# analog_in.net
KiCad netlist of a schematic drawn in Altium Designer
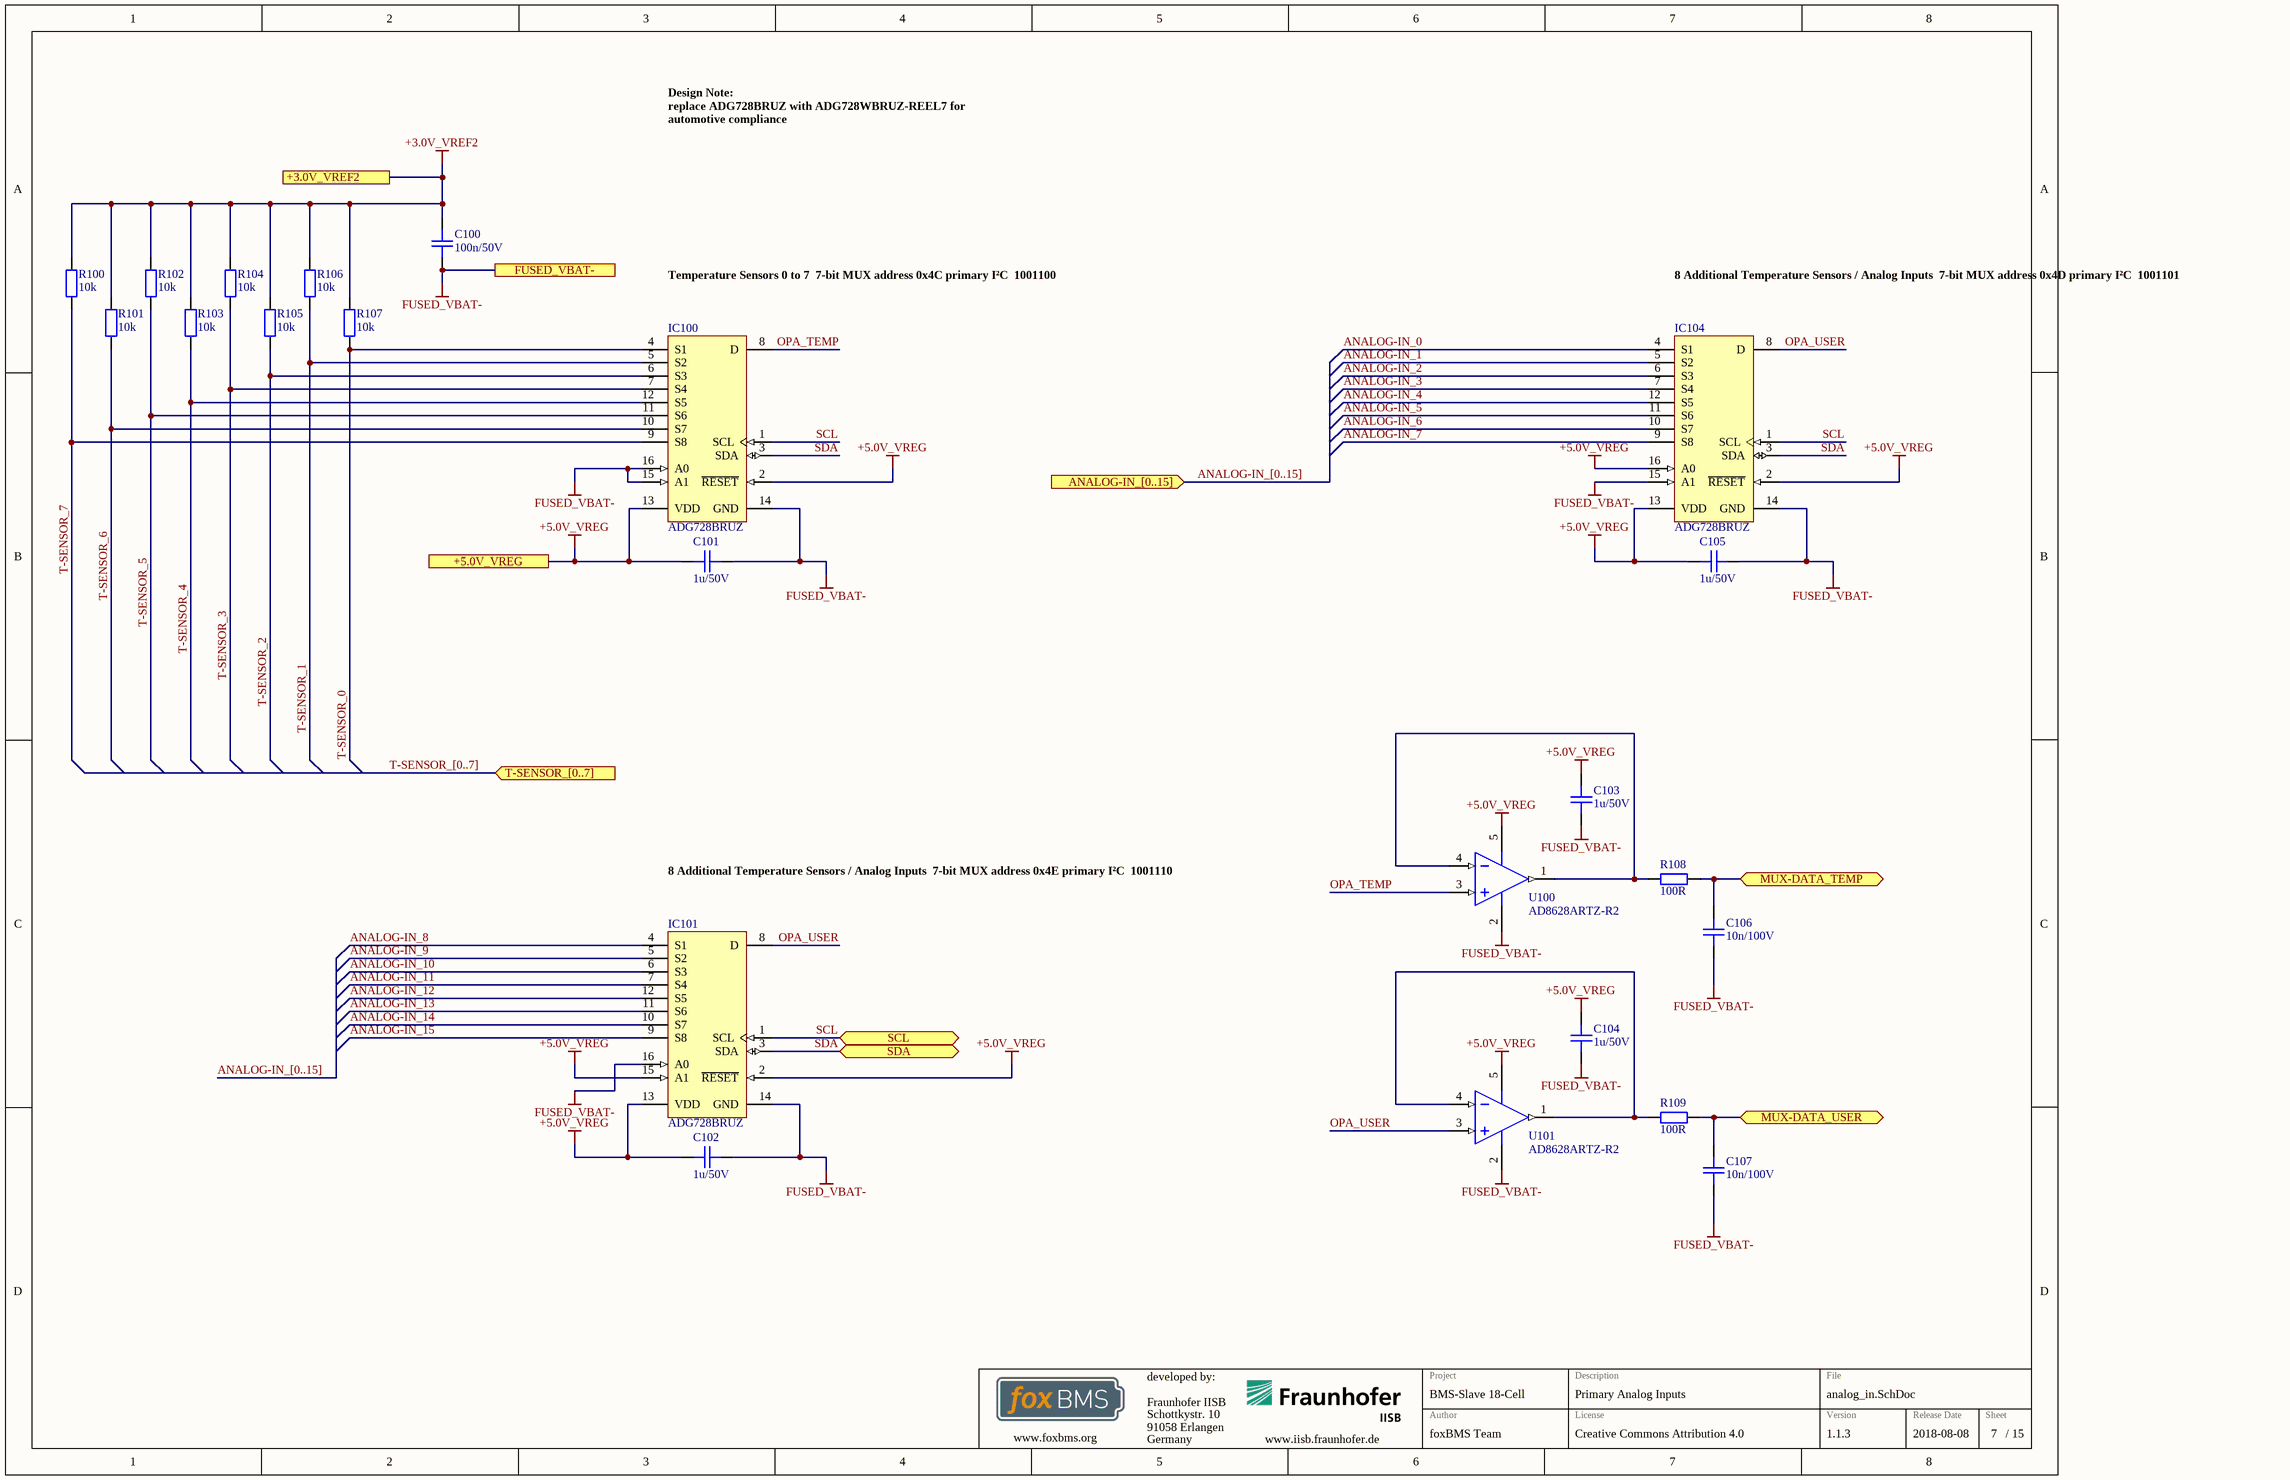
[diagram p0: analog_in.SchDoc]

(export (version "E")
  (design (tool "Eeschema 10.0.6"))
  (components
    (comp (ref "C100")
      (value "100n/50V")
      (footprint "CAPC1608X08N")
      (description "MLCC")
      (fields (field (name "PART NUMBER") "gen_C_ceramic_100n_50V_X7R_0603"))
      (libsource (lib "OE750") (part "C"))
    )
    (comp (ref "C101")
      (value "1u/50V")
      (footprint "CAPC2012X14N")
      (description "MLCC")
      (fields (field (name "PART NUMBER") "gen_C_ceramic_1u_50V_X7R_0805") (field (name "TOLERANCE") "± 10%"))
      (libsource (lib "OE750") (part "C"))
    )
    (comp (ref "C102")
      (value "1u/50V")
      (footprint "CAPC2012X14N")
      (description "MLCC")
      (fields (field (name "PART NUMBER") "gen_C_ceramic_1u_50V_X7R_0805") (field (name "TOLERANCE") "± 10%"))
      (libsource (lib "OE750") (part "C"))
    )
    (comp (ref "C103")
      (value "1u/50V")
      (footprint "CAPC2012X14N")
      (description "MLCC")
      (fields (field (name "PART NUMBER") "gen_C_ceramic_1u_50V_X7R_0805") (field (name "TOLERANCE") "± 10%"))
      (libsource (lib "OE750") (part "C"))
    )
    (comp (ref "C104")
      (value "1u/50V")
      (footprint "CAPC2012X14N")
      (description "MLCC")
      (fields (field (name "PART NUMBER") "gen_C_ceramic_1u_50V_X7R_0805") (field (name "TOLERANCE") "± 10%"))
      (libsource (lib "OE750") (part "C"))
    )
    (comp (ref "C105")
      (value "1u/50V")
      (footprint "CAPC2012X14N")
      (description "MLCC")
      (fields (field (name "PART NUMBER") "gen_C_ceramic_1u_50V_X7R_0805") (field (name "TOLERANCE") "± 10%"))
      (libsource (lib "OE750") (part "C"))
    )
    (comp (ref "C106")
      (value "10n/100V")
      (footprint "CAPC1608X08N")
      (description "MLCC")
      (fields (field (name "PART NUMBER") "gen_C_ceramic_10n_100V_X7R_0603"))
      (libsource (lib "OE750") (part "C"))
    )
    (comp (ref "C107")
      (value "10n/100V")
      (footprint "CAPC1608X08N")
      (description "MLCC")
      (fields (field (name "PART NUMBER") "gen_C_ceramic_10n_100V_X7R_0603"))
      (libsource (lib "OE750") (part "C"))
    )
    (comp (ref "IC100")
      (value "ADG728BRUZ")
      (footprint "ADI-RU-16_M")
      (fields (field (name "MANUFACTURER") "Analog Devices"))
      (libsource (lib "Altium Content Vault") (part "ADI-ADG728-RU-16"))
    )
    (comp (ref "IC101")
      (value "ADG728BRUZ")
      (footprint "ADI-RU-16_M")
      (fields (field (name "MANUFACTURER") "Analog Devices"))
      (libsource (lib "Altium Content Vault") (part "ADI-ADG728-RU-16"))
    )
    (comp (ref "IC104")
      (value "ADG728BRUZ")
      (footprint "ADI-RU-16_M")
      (fields (field (name "MANUFACTURER") "Analog Devices"))
      (libsource (lib "Altium Content Vault") (part "ADI-ADG728-RU-16"))
    )
    (comp (ref "R100")
      (value "10k")
      (footprint "RESC1608X05N")
      (description "SMD Resistor 10k 0603")
      (fields (field (name "PART NUMBER") "gen_R_10k_0603") (field (name "TOLERANCE") "1%"))
      (libsource (lib "OE750") (part "R"))
    )
    (comp (ref "R101")
      (value "10k")
      (footprint "RESC1608X05N")
      (description "SMD Resistor 10k 0603")
      (fields (field (name "PART NUMBER") "gen_R_10k_0603") (field (name "TOLERANCE") "1%"))
      (libsource (lib "OE750") (part "R"))
    )
    (comp (ref "R102")
      (value "10k")
      (footprint "RESC1608X05N")
      (description "SMD Resistor 10k 0603")
      (fields (field (name "PART NUMBER") "gen_R_10k_0603") (field (name "TOLERANCE") "1%"))
      (libsource (lib "OE750") (part "R"))
    )
    (comp (ref "R103")
      (value "10k")
      (footprint "RESC1608X05N")
      (description "SMD Resistor 10k 0603")
      (fields (field (name "PART NUMBER") "gen_R_10k_0603") (field (name "TOLERANCE") "1%"))
      (libsource (lib "OE750") (part "R"))
    )
    (comp (ref "R104")
      (value "10k")
      (footprint "RESC1608X05N")
      (description "SMD Resistor 10k 0603")
      (fields (field (name "PART NUMBER") "gen_R_10k_0603") (field (name "TOLERANCE") "1%"))
      (libsource (lib "OE750") (part "R"))
    )
    (comp (ref "R105")
      (value "10k")
      (footprint "RESC1608X05N")
      (description "SMD Resistor 10k 0603")
      (fields (field (name "PART NUMBER") "gen_R_10k_0603") (field (name "TOLERANCE") "1%"))
      (libsource (lib "OE750") (part "R"))
    )
    (comp (ref "R106")
      (value "10k")
      (footprint "RESC1608X05N")
      (description "SMD Resistor 10k 0603")
      (fields (field (name "PART NUMBER") "gen_R_10k_0603") (field (name "TOLERANCE") "1%"))
      (libsource (lib "OE750") (part "R"))
    )
    (comp (ref "R107")
      (value "10k")
      (footprint "RESC1608X05N")
      (description "SMD Resistor 10k 0603")
      (fields (field (name "PART NUMBER") "gen_R_10k_0603") (field (name "TOLERANCE") "1%"))
      (libsource (lib "OE750") (part "R"))
    )
    (comp (ref "R108")
      (value "100R")
      (footprint "RESC1608X05N")
      (description "SMD Resistor 100R 0603")
      (fields (field (name "PART NUMBER") "gen_R_100R_0603") (field (name "TOLERANCE") "1%"))
      (libsource (lib "OE750") (part "R"))
    )
    (comp (ref "R109")
      (value "100R")
      (footprint "RESC1608X05N")
      (description "SMD Resistor 100R 0603")
      (fields (field (name "PART NUMBER") "gen_R_100R_0603") (field (name "TOLERANCE") "1%"))
      (libsource (lib "OE750") (part "R"))
    )
    (comp (ref "U100")
      (value "AD8628ARTZ-R2")
      (footprint "ADI-RJ-5_M")
      (fields (field (name "MANUFACTURER") "Analog Devices") (field (name "GENERIC PART NUMBER") "AD8628"))
      (libsource (lib "Altium Content Vault") (part "ADI-ADxxxx-X-5"))
    )
    (comp (ref "U101")
      (value "AD8628ARTZ-R2")
      (footprint "ADI-RJ-5_M")
      (fields (field (name "MANUFACTURER") "Analog Devices") (field (name "GENERIC PART NUMBER") "AD8628"))
      (libsource (lib "Altium Content Vault") (part "ADI-ADxxxx-X-5"))
    )
  )
  (nets
    (net (code "1") (name "+3.0V_VREF2") (class "Default")
      (node (ref "C100") (pin "2") (pinfunction "2_2") (pintype "passive"))
      (node (ref "R100") (pin "2") (pinfunction "2_2") (pintype "passive"))
      (node (ref "R101") (pin "2") (pinfunction "2_2") (pintype "passive"))
      (node (ref "R102") (pin "2") (pinfunction "2_2") (pintype "passive"))
      (node (ref "R103") (pin "2") (pinfunction "2_2") (pintype "passive"))
      (node (ref "R104") (pin "2") (pinfunction "2_2") (pintype "passive"))
      (node (ref "R105") (pin "2") (pinfunction "2_2") (pintype "passive"))
      (node (ref "R106") (pin "2") (pinfunction "2_2") (pintype "passive"))
      (node (ref "R107") (pin "2") (pinfunction "2_2") (pintype "passive"))
    )
    (net (code "2") (name "+5.0V_VREG") (class "Default")
      (node (ref "C101") (pin "2") (pinfunction "2_2") (pintype "passive"))
      (node (ref "C102") (pin "2") (pinfunction "2_2") (pintype "passive"))
      (node (ref "C103") (pin "2") (pinfunction "2_2") (pintype "passive"))
      (node (ref "C104") (pin "2") (pinfunction "2_2") (pintype "passive"))
      (node (ref "C105") (pin "2") (pinfunction "2_2") (pintype "passive"))
      (node (ref "IC100") (pin "13") (pinfunction "VDD_13") (pintype "power_in"))
      (node (ref "IC100") (pin "2") (pinfunction "~{RESET}_2") (pintype "input"))
      (node (ref "IC101") (pin "13") (pinfunction "VDD_13") (pintype "power_in"))
      (node (ref "IC101") (pin "15") (pinfunction "A1_15") (pintype "input"))
      (node (ref "IC101") (pin "2") (pinfunction "~{RESET}_2") (pintype "input"))
      (node (ref "IC104") (pin "13") (pinfunction "VDD_13") (pintype "power_in"))
      (node (ref "IC104") (pin "16") (pinfunction "A0_16") (pintype "input"))
      (node (ref "IC104") (pin "2") (pinfunction "~{RESET}_2") (pintype "input"))
      (node (ref "U100") (pin "5") (pinfunction "+V_5") (pintype "power_in"))
      (node (ref "U101") (pin "5") (pinfunction "+V_5") (pintype "power_in"))
    )
    (net (code "3") (name "/ANALOG-IN_0") (class "Default")
      (node (ref "IC104") (pin "4") (pinfunction "S1_4") (pintype "passive"))
    )
    (net (code "4") (name "/ANALOG-IN_1") (class "Default")
      (node (ref "IC104") (pin "5") (pinfunction "S2_5") (pintype "passive"))
    )
    (net (code "5") (name "/ANALOG-IN_2") (class "Default")
      (node (ref "IC104") (pin "6") (pinfunction "S3_6") (pintype "passive"))
    )
    (net (code "6") (name "/ANALOG-IN_3") (class "Default")
      (node (ref "IC104") (pin "7") (pinfunction "S4_7") (pintype "passive"))
    )
    (net (code "7") (name "/ANALOG-IN_4") (class "Default")
      (node (ref "IC104") (pin "12") (pinfunction "S5_12") (pintype "passive"))
    )
    (net (code "8") (name "/ANALOG-IN_5") (class "Default")
      (node (ref "IC104") (pin "11") (pinfunction "S6_11") (pintype "passive"))
    )
    (net (code "9") (name "/ANALOG-IN_6") (class "Default")
      (node (ref "IC104") (pin "10") (pinfunction "S7_10") (pintype "passive"))
    )
    (net (code "10") (name "/ANALOG-IN_7") (class "Default")
      (node (ref "IC104") (pin "9") (pinfunction "S8_9") (pintype "passive"))
    )
    (net (code "11") (name "/ANALOG-IN_8") (class "Default")
      (node (ref "IC101") (pin "4") (pinfunction "S1_4") (pintype "passive"))
    )
    (net (code "12") (name "/ANALOG-IN_9") (class "Default")
      (node (ref "IC101") (pin "5") (pinfunction "S2_5") (pintype "passive"))
    )
    (net (code "13") (name "/ANALOG-IN_10") (class "Default")
      (node (ref "IC101") (pin "6") (pinfunction "S3_6") (pintype "passive"))
    )
    (net (code "14") (name "/ANALOG-IN_11") (class "Default")
      (node (ref "IC101") (pin "7") (pinfunction "S4_7") (pintype "passive"))
    )
    (net (code "15") (name "/ANALOG-IN_12") (class "Default")
      (node (ref "IC101") (pin "12") (pinfunction "S5_12") (pintype "passive"))
    )
    (net (code "16") (name "/ANALOG-IN_13") (class "Default")
      (node (ref "IC101") (pin "11") (pinfunction "S6_11") (pintype "passive"))
    )
    (net (code "17") (name "/ANALOG-IN_14") (class "Default")
      (node (ref "IC101") (pin "10") (pinfunction "S7_10") (pintype "passive"))
    )
    (net (code "18") (name "/ANALOG-IN_15") (class "Default")
      (node (ref "IC101") (pin "9") (pinfunction "S8_9") (pintype "passive"))
    )
    (net (code "20") (name "/MUX-DATA_TEMP") (class "Default")
      (node (ref "C106") (pin "2") (pinfunction "2_2") (pintype "passive"))
      (node (ref "R108") (pin "2") (pinfunction "2_2") (pintype "passive"))
    )
    (net (code "21") (name "/MUX-DATA_USER") (class "Default")
      (node (ref "C107") (pin "2") (pinfunction "2_2") (pintype "passive"))
      (node (ref "R109") (pin "2") (pinfunction "2_2") (pintype "passive"))
    )
    (net (code "22") (name "/OPA_TEMP") (class "Default")
      (node (ref "IC100") (pin "8") (pinfunction "D_8") (pintype "passive"))
      (node (ref "U100") (pin "3") (pinfunction "+IN_3") (pintype "input"))
    )
    (net (code "23") (name "/OPA_USER") (class "Default")
      (node (ref "IC101") (pin "8") (pinfunction "D_8") (pintype "passive"))
      (node (ref "IC104") (pin "8") (pinfunction "D_8") (pintype "passive"))
      (node (ref "U101") (pin "3") (pinfunction "+IN_3") (pintype "input"))
    )
    (net (code "24") (name "/SCL") (class "Default")
      (node (ref "IC100") (pin "1") (pinfunction "SCL_1") (pintype "input"))
      (node (ref "IC101") (pin "1") (pinfunction "SCL_1") (pintype "input"))
      (node (ref "IC104") (pin "1") (pinfunction "SCL_1") (pintype "input"))
    )
    (net (code "25") (name "/SDA") (class "Default")
      (node (ref "IC100") (pin "3") (pinfunction "SDA_3") (pintype "bidirectional"))
      (node (ref "IC101") (pin "3") (pinfunction "SDA_3") (pintype "bidirectional"))
      (node (ref "IC104") (pin "3") (pinfunction "SDA_3") (pintype "bidirectional"))
    )
    (net (code "26") (name "/T-SENSOR_0") (class "Default")
      (node (ref "IC100") (pin "4") (pinfunction "S1_4") (pintype "passive"))
      (node (ref "R107") (pin "1") (pinfunction "1_1") (pintype "passive"))
    )
    (net (code "27") (name "/T-SENSOR_1") (class "Default")
      (node (ref "IC100") (pin "5") (pinfunction "S2_5") (pintype "passive"))
      (node (ref "R106") (pin "1") (pinfunction "1_1") (pintype "passive"))
    )
    (net (code "28") (name "/T-SENSOR_2") (class "Default")
      (node (ref "IC100") (pin "6") (pinfunction "S3_6") (pintype "passive"))
      (node (ref "R105") (pin "1") (pinfunction "1_1") (pintype "passive"))
    )
    (net (code "29") (name "/T-SENSOR_3") (class "Default")
      (node (ref "IC100") (pin "7") (pinfunction "S4_7") (pintype "passive"))
      (node (ref "R104") (pin "1") (pinfunction "1_1") (pintype "passive"))
    )
    (net (code "30") (name "/T-SENSOR_4") (class "Default")
      (node (ref "IC100") (pin "12") (pinfunction "S5_12") (pintype "passive"))
      (node (ref "R103") (pin "1") (pinfunction "1_1") (pintype "passive"))
    )
    (net (code "31") (name "/T-SENSOR_5") (class "Default")
      (node (ref "IC100") (pin "11") (pinfunction "S6_11") (pintype "passive"))
      (node (ref "R102") (pin "1") (pinfunction "1_1") (pintype "passive"))
    )
    (net (code "32") (name "/T-SENSOR_6") (class "Default")
      (node (ref "IC100") (pin "10") (pinfunction "S7_10") (pintype "passive"))
      (node (ref "R101") (pin "1") (pinfunction "1_1") (pintype "passive"))
    )
    (net (code "33") (name "/T-SENSOR_7") (class "Default")
      (node (ref "IC100") (pin "9") (pinfunction "S8_9") (pintype "passive"))
      (node (ref "R100") (pin "1") (pinfunction "1_1") (pintype "passive"))
    )
    (net (code "35") (name "FUSED_VBAT-") (class "Default")
      (node (ref "C100") (pin "1") (pinfunction "1_1") (pintype "passive"))
      (node (ref "C101") (pin "1") (pinfunction "1_1") (pintype "passive"))
      (node (ref "C102") (pin "1") (pinfunction "1_1") (pintype "passive"))
      (node (ref "C103") (pin "1") (pinfunction "1_1") (pintype "passive"))
      (node (ref "C104") (pin "1") (pinfunction "1_1") (pintype "passive"))
      (node (ref "C105") (pin "1") (pinfunction "1_1") (pintype "passive"))
      (node (ref "C106") (pin "1") (pinfunction "1_1") (pintype "passive"))
      (node (ref "C107") (pin "1") (pinfunction "1_1") (pintype "passive"))
      (node (ref "IC100") (pin "14") (pinfunction "GND_14") (pintype "power_in"))
      (node (ref "IC100") (pin "15") (pinfunction "A1_15") (pintype "input"))
      (node (ref "IC100") (pin "16") (pinfunction "A0_16") (pintype "input"))
      (node (ref "IC101") (pin "14") (pinfunction "GND_14") (pintype "power_in"))
      (node (ref "IC101") (pin "16") (pinfunction "A0_16") (pintype "input"))
      (node (ref "IC104") (pin "14") (pinfunction "GND_14") (pintype "power_in"))
      (node (ref "IC104") (pin "15") (pinfunction "A1_15") (pintype "input"))
      (node (ref "U100") (pin "2") (pinfunction "-V_2") (pintype "power_in"))
      (node (ref "U101") (pin "2") (pinfunction "-V_2") (pintype "power_in"))
    )
    (net (code "36") (name "Net-(U100--IN)") (class "Default")
      (node (ref "R108") (pin "1") (pinfunction "1_1") (pintype "passive"))
      (node (ref "U100") (pin "1") (pinfunction "OUT_1") (pintype "output"))
      (node (ref "U100") (pin "4") (pinfunction "-IN_4") (pintype "input"))
    )
    (net (code "37") (name "Net-(U101--IN)") (class "Default")
      (node (ref "R109") (pin "1") (pinfunction "1_1") (pintype "passive"))
      (node (ref "U101") (pin "1") (pinfunction "OUT_1") (pintype "output"))
      (node (ref "U101") (pin "4") (pinfunction "-IN_4") (pintype "input"))
    )
  )
)
